# carte_bouton.net
KiCad netlist of a schematic drawn in EAGLE
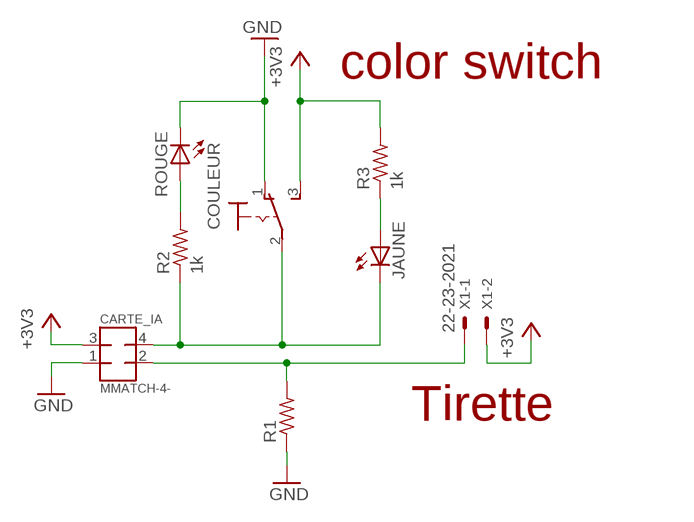
[diagram p0: schematic, sheet 1]

(export (version "E")
  (design (tool "Eeschema 10.0.6"))
  (components
    (comp (ref "CARTE_IA")
      (value "MMATCH-4-")
      (footprint "eagle-import:AMP-215079-4")
      (libsource (lib "eagle-import") (part "MMATCH-4-"))
    )
    (comp (ref "COULEUR")
      (value "320-916")
      (footprint "eagle-import:320-916")
      (libsource (lib "eagle-import") (part "320-916"))
    )
    (comp (ref "JAUNE")
      (value "LEDSML0805")
      (footprint "eagle-import:SML0805")
      (libsource (lib "eagle-import") (part "LEDSML0805"))
    )
    (comp (ref "R1")
      (value "R-US_R0805")
      (footprint "eagle-import:R0805")
      (libsource (lib "eagle-import") (part "R-US_R0805"))
    )
    (comp (ref "R2")
      (value "1k")
      (footprint "eagle-import:M0805")
      (libsource (lib "eagle-import") (part "R-US_M0805"))
    )
    (comp (ref "R3")
      (value "1k")
      (footprint "eagle-import:M0805")
      (libsource (lib "eagle-import") (part "R-US_M0805"))
    )
    (comp (ref "ROUGE")
      (value "LEDSML0805")
      (footprint "eagle-import:SML0805")
      (libsource (lib "eagle-import") (part "LEDSML0805"))
    )
    (comp (ref "X1")
      (value "22-23-2021")
      (footprint "eagle-import:22-23-2021")
      (fields (field (name "MF") "MOLEX"))
      (libsource (lib "eagle-import") (part "22-23-2021"))
    )
  )
  (nets
    (net (code "1") (name "+3V3") (class "Default")
      (node (ref "CARTE_IA") (pin "3") (pinfunction "7_3") (pintype "bidirectional"))
      (node (ref "COULEUR") (pin "3") (pinfunction "S_3") (pintype "passive"))
      (node (ref "R3") (pin "2") (pinfunction "2_2") (pintype "passive"))
      (node (ref "X1") (pin "2") (pinfunction "S_2") (pintype "passive"))
    )
    (net (code "2") (name "GND") (class "Default")
      (node (ref "CARTE_IA") (pin "1") (pinfunction "5_1") (pintype "bidirectional"))
      (node (ref "COULEUR") (pin "1") (pinfunction "O_1") (pintype "passive"))
      (node (ref "R1") (pin "1") (pinfunction "1_1") (pintype "passive"))
      (node (ref "ROUGE") (pin "C") (pinfunction "C_C") (pintype "passive"))
    )
    (net (code "3") (name "Net-(CARTE_IA-6)") (class "Default")
      (node (ref "CARTE_IA") (pin "2") (pinfunction "6_2") (pintype "bidirectional"))
      (node (ref "R1") (pin "2") (pinfunction "2_2") (pintype "passive"))
      (node (ref "X1") (pin "1") (pinfunction "S_1") (pintype "passive"))
    )
    (net (code "4") (name "Net-(CARTE_IA-8)") (class "Default")
      (node (ref "CARTE_IA") (pin "4") (pinfunction "8_4") (pintype "bidirectional"))
      (node (ref "COULEUR") (pin "2") (pinfunction "P_2") (pintype "passive"))
      (node (ref "JAUNE") (pin "C") (pinfunction "C_C") (pintype "passive"))
      (node (ref "R2") (pin "1") (pinfunction "1_1") (pintype "passive"))
    )
    (net (code "5") (name "Net-(JAUNE-PadA)") (class "Default")
      (node (ref "JAUNE") (pin "A") (pinfunction "A_A") (pintype "passive"))
      (node (ref "R3") (pin "1") (pinfunction "1_1") (pintype "passive"))
    )
    (net (code "6") (name "Net-(R2-Pad2)") (class "Default")
      (node (ref "R2") (pin "2") (pinfunction "2_2") (pintype "passive"))
      (node (ref "ROUGE") (pin "A") (pinfunction "A_A") (pintype "passive"))
    )
  )
)
